# mach_dk_role.net
KiCad netlist of a schematic drawn in Altium Designer
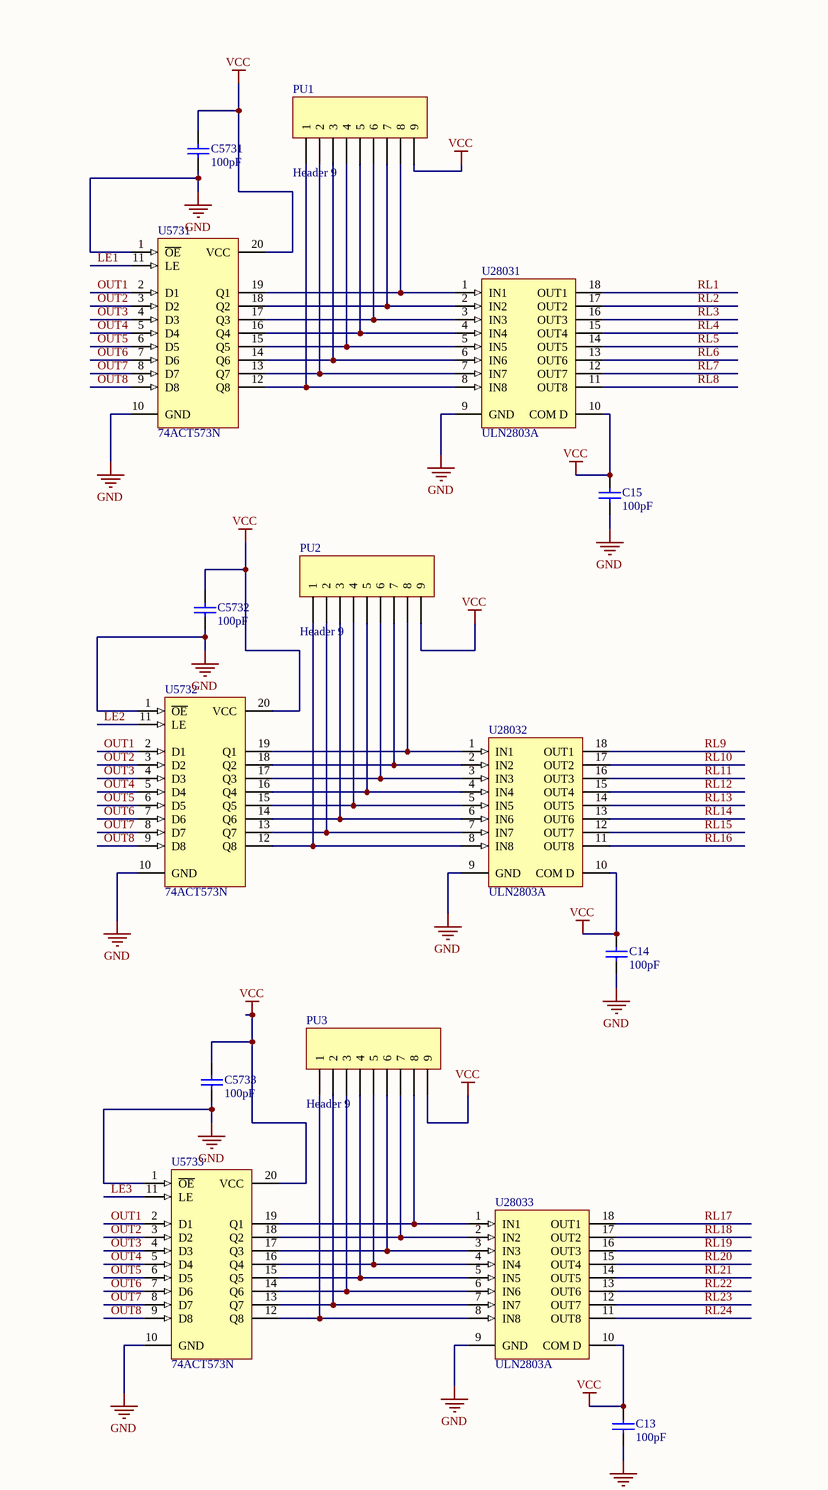
[diagram p0: mach dk role.SchDoc, top right]
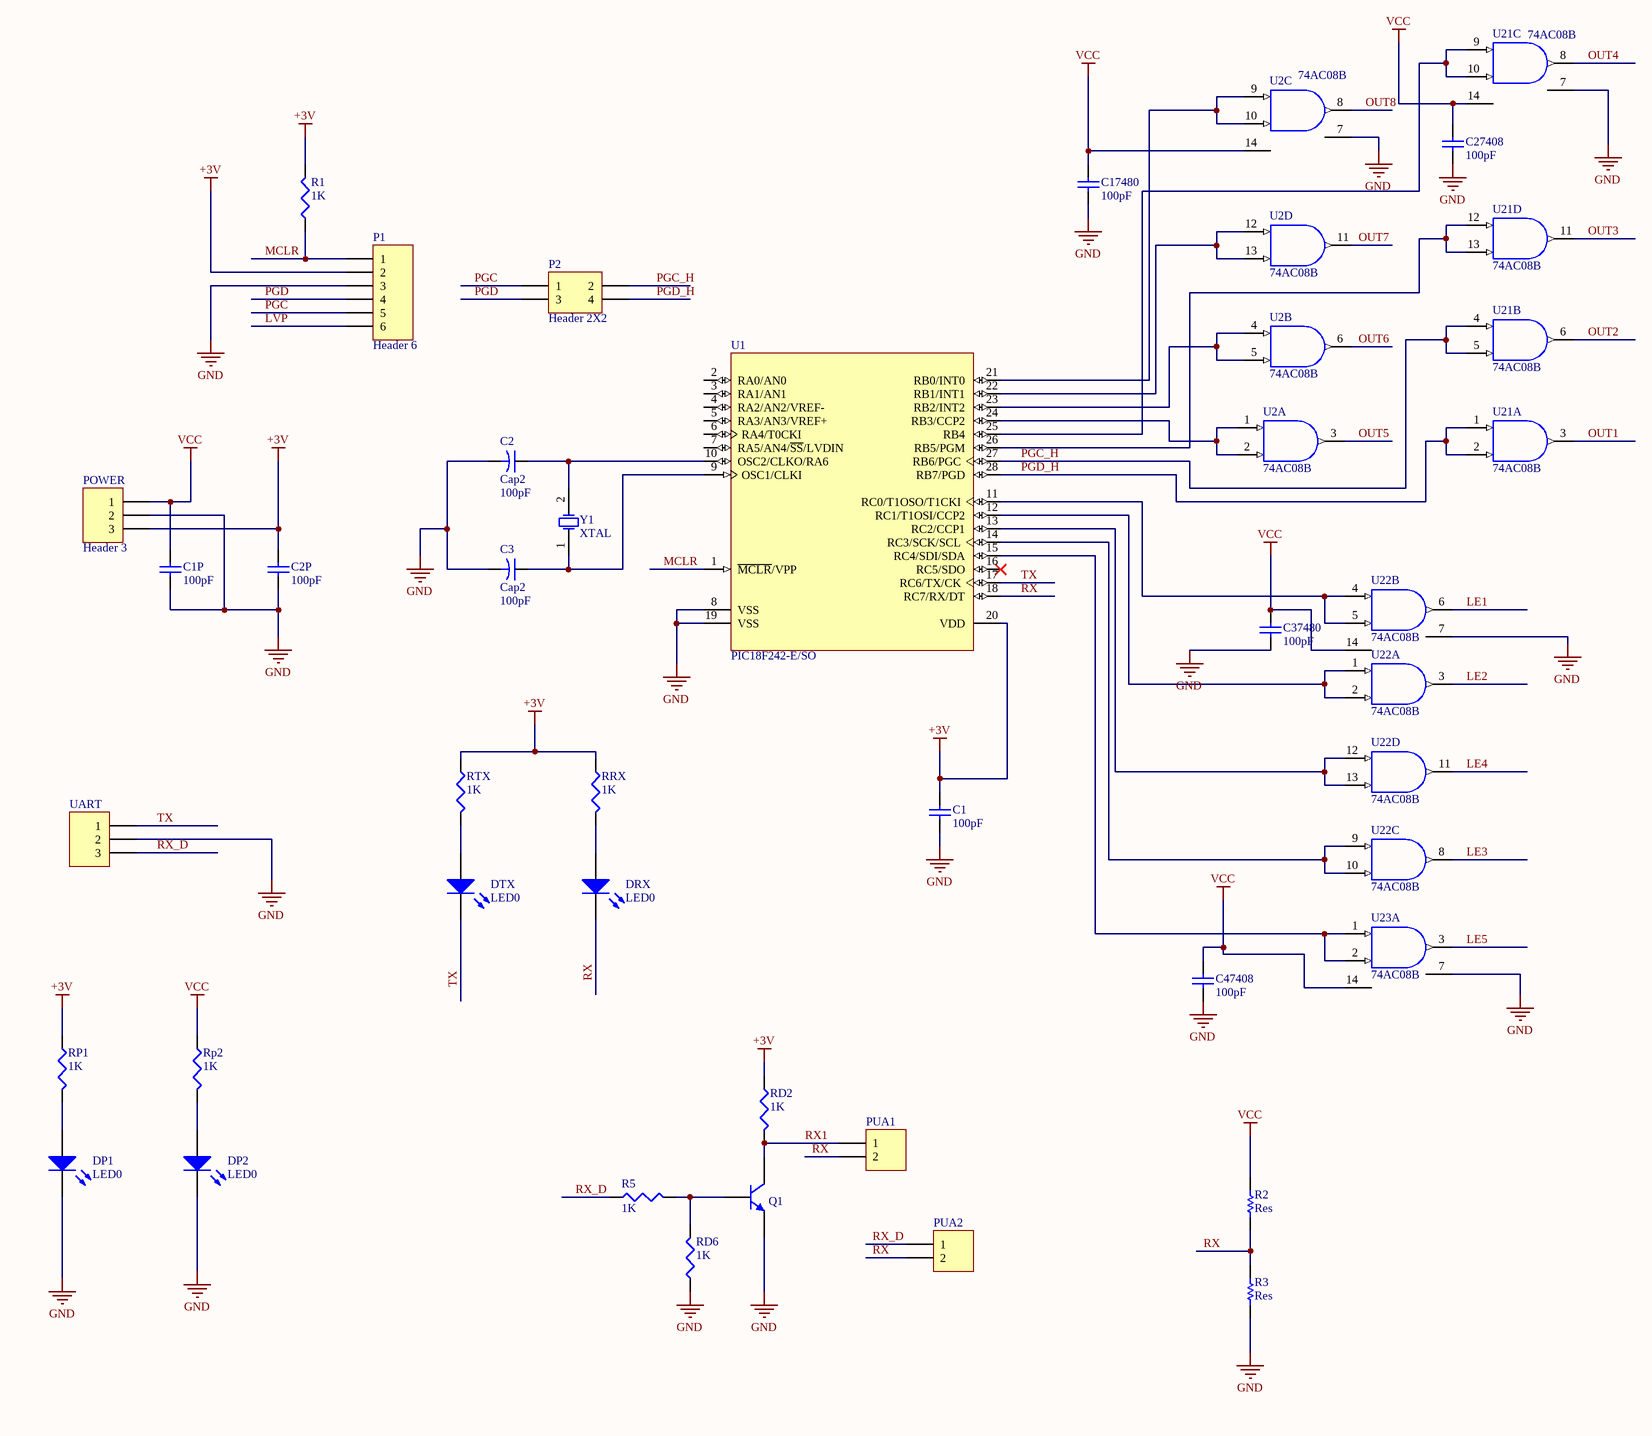
[diagram p1: mach dk role.SchDoc, bottom left]
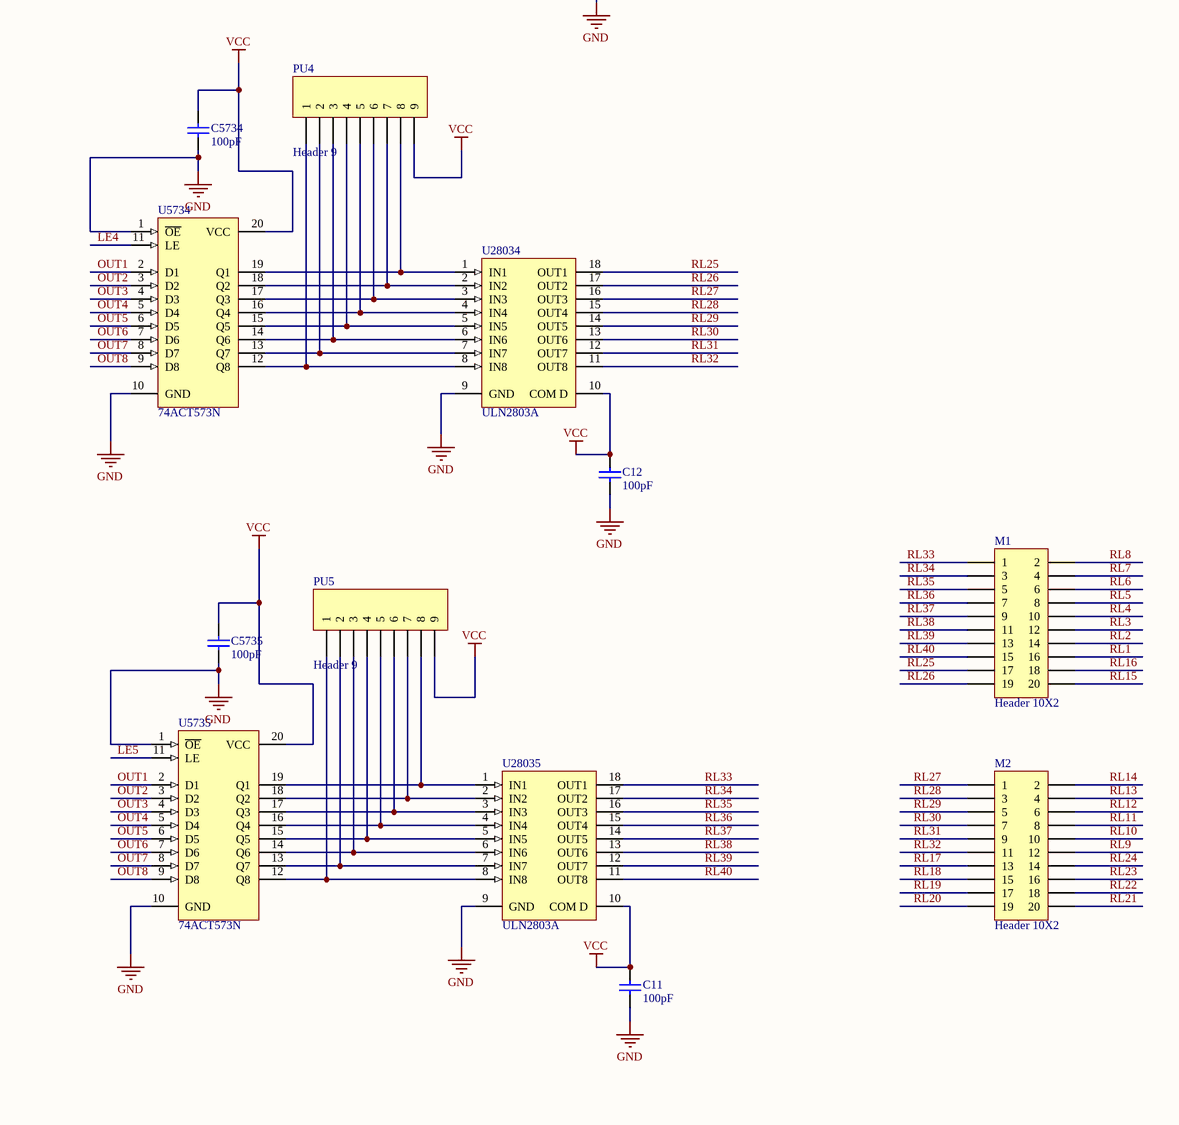
[diagram p2: mach dk role.SchDoc, bottom right]

(export (version "E")
  (design (tool "Eeschema 10.0.6"))
  (components
    (comp (ref "C1")
      (value "100pF")
      (footprint "RAD-0.3")
      (description "Capacitor")
      (fields (field (name "Comment") "Cap") (field (name "PUBLISHER") "Altium Limited"))
      (libsource (lib "Miscellaneous Devices") (part "Cap"))
    )
    (comp (ref "C1P")
      (value "100pF")
      (footprint "RAD-0.3")
      (description "Capacitor")
      (fields (field (name "Comment") "Cap") (field (name "PUBLISHER") "Altium Limited"))
      (libsource (lib "Miscellaneous Devices") (part "Cap"))
    )
    (comp (ref "C2")
      (value "Cap2")
      (footprint "CAPR5-4X5")
      (description "Capacitor")
      (fields (field (name "ALTIUM_VALUE") "100pF") (field (name "PUBLISHER") "Altium Limited"))
      (libsource (lib "Miscellaneous Devices") (part "Cap2"))
    )
    (comp (ref "C2P")
      (value "100pF")
      (footprint "RAD-0.3")
      (description "Capacitor")
      (fields (field (name "Comment") "Cap") (field (name "PUBLISHER") "Altium Limited"))
      (libsource (lib "Miscellaneous Devices") (part "Cap"))
    )
    (comp (ref "C3")
      (value "Cap2")
      (footprint "CAPR5-4X5")
      (description "Capacitor")
      (fields (field (name "ALTIUM_VALUE") "100pF") (field (name "PUBLISHER") "Altium Limited"))
      (libsource (lib "Miscellaneous Devices") (part "Cap2"))
    )
    (comp (ref "C11")
      (value "100pF")
      (footprint "RAD-0.3")
      (description "Capacitor")
      (fields (field (name "Comment") "Cap") (field (name "PUBLISHER") "Altium Limited"))
      (libsource (lib "Miscellaneous Devices") (part "Cap"))
    )
    (comp (ref "C12")
      (value "100pF")
      (footprint "RAD-0.3")
      (description "Capacitor")
      (fields (field (name "Comment") "Cap") (field (name "PUBLISHER") "Altium Limited"))
      (libsource (lib "Miscellaneous Devices") (part "Cap"))
    )
    (comp (ref "C13")
      (value "100pF")
      (footprint "RAD-0.3")
      (description "Capacitor")
      (fields (field (name "Comment") "Cap") (field (name "PUBLISHER") "Altium Limited"))
      (libsource (lib "Miscellaneous Devices") (part "Cap"))
    )
    (comp (ref "C14")
      (value "100pF")
      (footprint "RAD-0.3")
      (description "Capacitor")
      (fields (field (name "Comment") "Cap") (field (name "PUBLISHER") "Altium Limited"))
      (libsource (lib "Miscellaneous Devices") (part "Cap"))
    )
    (comp (ref "C15")
      (value "100pF")
      (footprint "RAD-0.3")
      (description "Capacitor")
      (fields (field (name "Comment") "Cap") (field (name "PUBLISHER") "Altium Limited"))
      (libsource (lib "Miscellaneous Devices") (part "Cap"))
    )
    (comp (ref "C5731")
      (value "100pF")
      (footprint "RAD-0.3")
      (description "Capacitor")
      (fields (field (name "Comment") "Cap") (field (name "PUBLISHER") "Altium Limited"))
      (libsource (lib "Miscellaneous Devices") (part "Cap"))
    )
    (comp (ref "C5732")
      (value "100pF")
      (footprint "RAD-0.3")
      (description "Capacitor")
      (fields (field (name "Comment") "Cap") (field (name "PUBLISHER") "Altium Limited"))
      (libsource (lib "Miscellaneous Devices") (part "Cap"))
    )
    (comp (ref "C5733")
      (value "100pF")
      (footprint "RAD-0.3")
      (description "Capacitor")
      (fields (field (name "Comment") "Cap") (field (name "PUBLISHER") "Altium Limited"))
      (libsource (lib "Miscellaneous Devices") (part "Cap"))
    )
    (comp (ref "C5734")
      (value "100pF")
      (footprint "RAD-0.3")
      (description "Capacitor")
      (fields (field (name "Comment") "Cap") (field (name "PUBLISHER") "Altium Limited"))
      (libsource (lib "Miscellaneous Devices") (part "Cap"))
    )
    (comp (ref "C5735")
      (value "100pF")
      (footprint "RAD-0.3")
      (description "Capacitor")
      (fields (field (name "Comment") "Cap") (field (name "PUBLISHER") "Altium Limited"))
      (libsource (lib "Miscellaneous Devices") (part "Cap"))
    )
    (comp (ref "C17480")
      (value "100pF")
      (footprint "RAD-0.3")
      (description "Capacitor")
      (fields (field (name "Comment") "Cap") (field (name "PUBLISHER") "Altium Limited"))
      (libsource (lib "Miscellaneous Devices") (part "Cap"))
    )
    (comp (ref "C27408")
      (value "100pF")
      (footprint "RAD-0.3")
      (description "Capacitor")
      (fields (field (name "Comment") "Cap") (field (name "PUBLISHER") "Altium Limited"))
      (libsource (lib "Miscellaneous Devices") (part "Cap"))
    )
    (comp (ref "C37480")
      (value "100pF")
      (footprint "RAD-0.3")
      (description "Capacitor")
      (fields (field (name "Comment") "Cap") (field (name "PUBLISHER") "Altium Limited"))
      (libsource (lib "Miscellaneous Devices") (part "Cap"))
    )
    (comp (ref "C47408")
      (value "100pF")
      (footprint "RAD-0.3")
      (description "Capacitor")
      (fields (field (name "Comment") "Cap") (field (name "PUBLISHER") "Altium Limited"))
      (libsource (lib "Miscellaneous Devices") (part "Cap"))
    )
    (comp (ref "DP1")
      (value "LED0")
      (footprint "LED-0")
      (description "Typical INFRARED GaAs LED")
      (fields (field (name "PUBLISHER") "Altium Limited"))
      (libsource (lib "Miscellaneous Devices") (part "LED0"))
    )
    (comp (ref "DP2")
      (value "LED0")
      (footprint "LED-0")
      (description "Typical INFRARED GaAs LED")
      (fields (field (name "PUBLISHER") "Altium Limited"))
      (libsource (lib "Miscellaneous Devices") (part "LED0"))
    )
    (comp (ref "DRX")
      (value "LED0")
      (footprint "LED-0")
      (description "Typical INFRARED GaAs LED")
      (fields (field (name "PUBLISHER") "Altium Limited"))
      (libsource (lib "Miscellaneous Devices") (part "LED0"))
    )
    (comp (ref "DTX")
      (value "LED0")
      (footprint "LED-0")
      (description "Typical INFRARED GaAs LED")
      (fields (field (name "PUBLISHER") "Altium Limited"))
      (libsource (lib "Miscellaneous Devices") (part "LED0"))
    )
    (comp (ref "M1")
      (value "Header 10X2")
      (footprint "HDR2X10")
      (description "Header, 10-Pin, Dual row")
      (fields (field (name "PUBLISHER") "Altium Limited"))
      (libsource (lib "Miscellaneous Connectors") (part "Header 10X2"))
    )
    (comp (ref "M2")
      (value "Header 10X2")
      (footprint "HDR2X10")
      (description "Header, 10-Pin, Dual row")
      (fields (field (name "PUBLISHER") "Altium Limited"))
      (libsource (lib "Miscellaneous Connectors") (part "Header 10X2"))
    )
    (comp (ref "P1")
      (value "Header 6")
      (footprint "HDR1X6")
      (description "Header, 6-Pin")
      (fields (field (name "PUBLISHER") "Altium Limited"))
      (libsource (lib "Miscellaneous Connectors") (part "Header 6"))
    )
    (comp (ref "P2")
      (value "Header 2X2")
      (footprint "HDR2X2")
      (description "Header, 2-Pin, Dual row")
      (fields (field (name "PUBLISHER") "Altium Limited"))
      (libsource (lib "Miscellaneous Connectors") (part "Header 2X2"))
    )
    (comp (ref "POWER")
      (value "Header 3")
      (footprint "HDR1X3")
      (description "Header, 3-Pin")
      (fields (field (name "PUBLISHER") "Altium Limited"))
      (libsource (lib "Miscellaneous Connectors") (part "Header 3"))
    )
    (comp (ref "PU1")
      (value "Header 9")
      (footprint "HDR1X9")
      (description "Header, 9-Pin")
      (fields (field (name "PUBLISHER") "Altium Limited"))
      (libsource (lib "Miscellaneous Connectors") (part "Header 9"))
    )
    (comp (ref "PU2")
      (value "Header 9")
      (footprint "HDR1X9")
      (description "Header, 9-Pin")
      (fields (field (name "PUBLISHER") "Altium Limited"))
      (libsource (lib "Miscellaneous Connectors") (part "Header 9"))
    )
    (comp (ref "PU3")
      (value "Header 9")
      (footprint "HDR1X9")
      (description "Header, 9-Pin")
      (fields (field (name "PUBLISHER") "Altium Limited"))
      (libsource (lib "Miscellaneous Connectors") (part "Header 9"))
    )
    (comp (ref "PU4")
      (value "Header 9")
      (footprint "HDR1X9")
      (description "Header, 9-Pin")
      (fields (field (name "PUBLISHER") "Altium Limited"))
      (libsource (lib "Miscellaneous Connectors") (part "Header 9"))
    )
    (comp (ref "PU5")
      (value "Header 9")
      (footprint "HDR1X9")
      (description "Header, 9-Pin")
      (fields (field (name "PUBLISHER") "Altium Limited"))
      (libsource (lib "Miscellaneous Connectors") (part "Header 9"))
    )
    (comp (ref "PUA1")
      (value "Header 2")
      (footprint "HDR1X2")
      (description "Header, 2-Pin")
      (fields (field (name "PUBLISHER") "Altium Limited"))
      (libsource (lib "Miscellaneous Connectors") (part "Header 2"))
    )
    (comp (ref "PUA2")
      (value "Header 2")
      (footprint "HDR1X2")
      (description "Header, 2-Pin")
      (fields (field (name "PUBLISHER") "Altium Limited"))
      (libsource (lib "Miscellaneous Connectors") (part "Header 2"))
    )
    (comp (ref "Q1")
      (value "C1815")
      (footprint "Device:C1815")
      (libsource (lib "Device_Component") (part "C1815"))
    )
    (comp (ref "R1")
      (value "1K")
      (footprint "J1-0603")
      (description "Resistor")
      (fields (field (name "Comment") "Res3") (field (name "PUBLISHER") "Altium Limited"))
      (libsource (lib "Miscellaneous Devices") (part "Res3"))
    )
    (comp (ref "R2")
      (value "Res")
      (footprint "Device:R_Nor")
      (libsource (lib "Device_Component") (part "Res"))
    )
    (comp (ref "R3")
      (value "Res")
      (footprint "Device:R_Nor")
      (libsource (lib "Device_Component") (part "Res"))
    )
    (comp (ref "R5")
      (value "1K")
      (footprint "J1-0603")
      (description "Resistor")
      (fields (field (name "Comment") "Res3") (field (name "PUBLISHER") "Altium Limited"))
      (libsource (lib "Miscellaneous Devices") (part "Res3"))
    )
    (comp (ref "RD2")
      (value "1K")
      (footprint "J1-0603")
      (description "Resistor")
      (fields (field (name "Comment") "Res3") (field (name "PUBLISHER") "Altium Limited"))
      (libsource (lib "Miscellaneous Devices") (part "Res3"))
    )
    (comp (ref "RD6")
      (value "1K")
      (footprint "J1-0603")
      (description "Resistor")
      (fields (field (name "Comment") "Res3") (field (name "PUBLISHER") "Altium Limited"))
      (libsource (lib "Miscellaneous Devices") (part "Res3"))
    )
    (comp (ref "RP1")
      (value "1K")
      (footprint "J1-0603")
      (description "Resistor")
      (fields (field (name "Comment") "Res3") (field (name "PUBLISHER") "Altium Limited"))
      (libsource (lib "Miscellaneous Devices") (part "Res3"))
    )
    (comp (ref "Rp2")
      (value "1K")
      (footprint "J1-0603")
      (description "Resistor")
      (fields (field (name "Comment") "Res3") (field (name "PUBLISHER") "Altium Limited"))
      (libsource (lib "Miscellaneous Devices") (part "Res3"))
    )
    (comp (ref "RRX")
      (value "1K")
      (footprint "J1-0603")
      (description "Resistor")
      (fields (field (name "Comment") "Res3") (field (name "PUBLISHER") "Altium Limited"))
      (libsource (lib "Miscellaneous Devices") (part "Res3"))
    )
    (comp (ref "RTX")
      (value "1K")
      (footprint "J1-0603")
      (description "Resistor")
      (fields (field (name "Comment") "Res3") (field (name "PUBLISHER") "Altium Limited"))
      (libsource (lib "Miscellaneous Devices") (part "Res3"))
    )
    (comp (ref "U1")
      (value "PIC18F242-E/SO")
      (footprint "SOIC300-28_N")
      (fields (field (name "PUBLISHER") "Altium Limited"))
      (libsource (lib "Microchip Microcontroller 8-Bit PIC18") (part "PIC18F242-E/SO"))
    )
    (comp (ref "U2")
      (value "74AC08B")
      (footprint "DIP14")
      (description "Quad 2-Input AND Gate")
      (fields (field (name "PUBLISHER") "Altium Limited"))
      (libsource (lib "ST Logic Gate") (part "74AC08B"))
    )
    (comp (ref "U21")
      (value "74AC08B")
      (footprint "DIP14")
      (description "Quad 2-Input AND Gate")
      (fields (field (name "PUBLISHER") "Altium Limited"))
      (libsource (lib "ST Logic Gate") (part "74AC08B"))
    )
    (comp (ref "U22")
      (value "74AC08B")
      (footprint "DIP14")
      (description "Quad 2-Input AND Gate")
      (fields (field (name "PUBLISHER") "Altium Limited"))
      (libsource (lib "ST Logic Gate") (part "74AC08B"))
    )
    (comp (ref "U23")
      (value "74AC08B")
      (footprint "DIP14")
      (description "Quad 2-Input AND Gate")
      (fields (field (name "PUBLISHER") "Altium Limited"))
      (libsource (lib "ST Logic Gate") (part "74AC08B"))
    )
    (comp (ref "U5731")
      (value "74ACT573N")
      (footprint "N020C")
      (description "Octal D-Type Transparent Latch with 3-State Outputs")
      (fields (field (name "PUBLISHER") "Altium Limited"))
      (libsource (lib "TI Logic Latch") (part "74ACT573N"))
    )
    (comp (ref "U5732")
      (value "74ACT573N")
      (footprint "N020C")
      (description "Octal D-Type Transparent Latch with 3-State Outputs")
      (fields (field (name "PUBLISHER") "Altium Limited"))
      (libsource (lib "TI Logic Latch") (part "74ACT573N"))
    )
    (comp (ref "U5733")
      (value "74ACT573N")
      (footprint "N020C")
      (description "Octal D-Type Transparent Latch with 3-State Outputs")
      (fields (field (name "PUBLISHER") "Altium Limited"))
      (libsource (lib "TI Logic Latch") (part "74ACT573N"))
    )
    (comp (ref "U5734")
      (value "74ACT573N")
      (footprint "N020C")
      (description "Octal D-Type Transparent Latch with 3-State Outputs")
      (fields (field (name "PUBLISHER") "Altium Limited"))
      (libsource (lib "TI Logic Latch") (part "74ACT573N"))
    )
    (comp (ref "U5735")
      (value "74ACT573N")
      (footprint "N020C")
      (description "Octal D-Type Transparent Latch with 3-State Outputs")
      (fields (field (name "PUBLISHER") "Altium Limited"))
      (libsource (lib "TI Logic Latch") (part "74ACT573N"))
    )
    (comp (ref "U28031")
      (value "ULN2803A")
      (footprint "DIP18")
      (description "Eight Darlington Array")
      (fields (field (name "PUBLISHER") "Altium Limited"))
      (libsource (lib "ST Interface Darlington Driver") (part "ULN2803A"))
    )
    (comp (ref "U28032")
      (value "ULN2803A")
      (footprint "DIP18")
      (description "Eight Darlington Array")
      (fields (field (name "PUBLISHER") "Altium Limited"))
      (libsource (lib "ST Interface Darlington Driver") (part "ULN2803A"))
    )
    (comp (ref "U28033")
      (value "ULN2803A")
      (footprint "DIP18")
      (description "Eight Darlington Array")
      (fields (field (name "PUBLISHER") "Altium Limited"))
      (libsource (lib "ST Interface Darlington Driver") (part "ULN2803A"))
    )
    (comp (ref "U28034")
      (value "ULN2803A")
      (footprint "DIP18")
      (description "Eight Darlington Array")
      (fields (field (name "PUBLISHER") "Altium Limited"))
      (libsource (lib "ST Interface Darlington Driver") (part "ULN2803A"))
    )
    (comp (ref "U28035")
      (value "ULN2803A")
      (footprint "DIP18")
      (description "Eight Darlington Array")
      (fields (field (name "PUBLISHER") "Altium Limited"))
      (libsource (lib "ST Interface Darlington Driver") (part "ULN2803A"))
    )
    (comp (ref "UART")
      (value "Header 3")
      (footprint "HDR1X3")
      (description "Header, 3-Pin")
      (fields (field (name "PUBLISHER") "Altium Limited"))
      (libsource (lib "Miscellaneous Connectors") (part "Header 3"))
    )
    (comp (ref "Y1")
      (value "XTAL")
      (footprint "R38")
      (description "Crystal Oscillator")
      (fields (field (name "PUBLISHER") "Altium Limited"))
      (libsource (lib "Miscellaneous Devices") (part "XTAL"))
    )
  )
  (nets
    (net (code "1") (name "+3V") (class "Default")
      (node (ref "C1") (pin "1") (pinfunction "1_1") (pintype "passive"))
      (node (ref "C2P") (pin "1") (pinfunction "1_1") (pintype "passive"))
      (node (ref "P1") (pin "2") (pinfunction "2_2") (pintype "passive"))
      (node (ref "POWER") (pin "3") (pinfunction "3_3") (pintype "passive"))
      (node (ref "R1") (pin "2") (pinfunction "2_2") (pintype "passive"))
      (node (ref "RD2") (pin "1") (pinfunction "1_1") (pintype "passive"))
      (node (ref "RP1") (pin "1") (pinfunction "1_1") (pintype "passive"))
      (node (ref "RRX") (pin "1") (pinfunction "1_1") (pintype "passive"))
      (node (ref "RTX") (pin "1") (pinfunction "1_1") (pintype "passive"))
      (node (ref "U1") (pin "20") (pinfunction "VDD_20") (pintype "power_in"))
    )
    (net (code "2") (name "/LE1") (class "Default")
      (node (ref "U22") (pin "6") (pinfunction "Y_6") (pintype "output"))
      (node (ref "U5731") (pin "11") (pinfunction "LE_11") (pintype "input"))
    )
    (net (code "3") (name "/LE2") (class "Default")
      (node (ref "U22") (pin "3") (pinfunction "Y_3") (pintype "output"))
      (node (ref "U5732") (pin "11") (pinfunction "LE_11") (pintype "input"))
    )
    (net (code "4") (name "/LE3") (class "Default")
      (node (ref "U22") (pin "8") (pinfunction "Y_8") (pintype "output"))
      (node (ref "U5733") (pin "11") (pinfunction "LE_11") (pintype "input"))
    )
    (net (code "5") (name "/LE4") (class "Default")
      (node (ref "U22") (pin "11") (pinfunction "Y_11") (pintype "output"))
      (node (ref "U5734") (pin "11") (pinfunction "LE_11") (pintype "input"))
    )
    (net (code "6") (name "/LE5") (class "Default")
      (node (ref "U23") (pin "3") (pinfunction "Y_3") (pintype "output"))
      (node (ref "U5735") (pin "11") (pinfunction "LE_11") (pintype "input"))
    )
    (net (code "7") (name "/LVP") (class "Default")
      (node (ref "P1") (pin "6") (pinfunction "6_6") (pintype "passive"))
    )
    (net (code "8") (name "/MCLR") (class "Default")
      (node (ref "P1") (pin "1") (pinfunction "1_1") (pintype "passive"))
      (node (ref "R1") (pin "1") (pinfunction "1_1") (pintype "passive"))
      (node (ref "U1") (pin "1") (pinfunction "~{MCLR}/VPP_1") (pintype "input"))
    )
    (net (code "9") (name "/OUT1") (class "Default")
      (node (ref "U21") (pin "3") (pinfunction "Y_3") (pintype "output"))
      (node (ref "U5731") (pin "2") (pinfunction "D1_2") (pintype "input"))
      (node (ref "U5732") (pin "2") (pinfunction "D1_2") (pintype "input"))
      (node (ref "U5733") (pin "2") (pinfunction "D1_2") (pintype "input"))
      (node (ref "U5734") (pin "2") (pinfunction "D1_2") (pintype "input"))
      (node (ref "U5735") (pin "2") (pinfunction "D1_2") (pintype "input"))
    )
    (net (code "10") (name "/OUT2") (class "Default")
      (node (ref "U21") (pin "6") (pinfunction "Y_6") (pintype "output"))
      (node (ref "U5731") (pin "3") (pinfunction "D2_3") (pintype "input"))
      (node (ref "U5732") (pin "3") (pinfunction "D2_3") (pintype "input"))
      (node (ref "U5733") (pin "3") (pinfunction "D2_3") (pintype "input"))
      (node (ref "U5734") (pin "3") (pinfunction "D2_3") (pintype "input"))
      (node (ref "U5735") (pin "3") (pinfunction "D2_3") (pintype "input"))
    )
    (net (code "11") (name "/OUT3") (class "Default")
      (node (ref "U21") (pin "11") (pinfunction "Y_11") (pintype "output"))
      (node (ref "U5731") (pin "4") (pinfunction "D3_4") (pintype "input"))
      (node (ref "U5732") (pin "4") (pinfunction "D3_4") (pintype "input"))
      (node (ref "U5733") (pin "4") (pinfunction "D3_4") (pintype "input"))
      (node (ref "U5734") (pin "4") (pinfunction "D3_4") (pintype "input"))
      (node (ref "U5735") (pin "4") (pinfunction "D3_4") (pintype "input"))
    )
    (net (code "12") (name "/OUT4") (class "Default")
      (node (ref "U21") (pin "8") (pinfunction "Y_8") (pintype "output"))
      (node (ref "U5731") (pin "5") (pinfunction "D4_5") (pintype "input"))
      (node (ref "U5732") (pin "5") (pinfunction "D4_5") (pintype "input"))
      (node (ref "U5733") (pin "5") (pinfunction "D4_5") (pintype "input"))
      (node (ref "U5734") (pin "5") (pinfunction "D4_5") (pintype "input"))
      (node (ref "U5735") (pin "5") (pinfunction "D4_5") (pintype "input"))
    )
    (net (code "13") (name "/OUT5") (class "Default")
      (node (ref "U2") (pin "3") (pinfunction "Y_3") (pintype "output"))
      (node (ref "U5731") (pin "6") (pinfunction "D5_6") (pintype "input"))
      (node (ref "U5732") (pin "6") (pinfunction "D5_6") (pintype "input"))
      (node (ref "U5733") (pin "6") (pinfunction "D5_6") (pintype "input"))
      (node (ref "U5734") (pin "6") (pinfunction "D5_6") (pintype "input"))
      (node (ref "U5735") (pin "6") (pinfunction "D5_6") (pintype "input"))
    )
    (net (code "14") (name "/OUT6") (class "Default")
      (node (ref "U2") (pin "6") (pinfunction "Y_6") (pintype "output"))
      (node (ref "U5731") (pin "7") (pinfunction "D6_7") (pintype "input"))
      (node (ref "U5732") (pin "7") (pinfunction "D6_7") (pintype "input"))
      (node (ref "U5733") (pin "7") (pinfunction "D6_7") (pintype "input"))
      (node (ref "U5734") (pin "7") (pinfunction "D6_7") (pintype "input"))
      (node (ref "U5735") (pin "7") (pinfunction "D6_7") (pintype "input"))
    )
    (net (code "15") (name "/OUT7") (class "Default")
      (node (ref "U2") (pin "11") (pinfunction "Y_11") (pintype "output"))
      (node (ref "U5731") (pin "8") (pinfunction "D7_8") (pintype "input"))
      (node (ref "U5732") (pin "8") (pinfunction "D7_8") (pintype "input"))
      (node (ref "U5733") (pin "8") (pinfunction "D7_8") (pintype "input"))
      (node (ref "U5734") (pin "8") (pinfunction "D7_8") (pintype "input"))
      (node (ref "U5735") (pin "8") (pinfunction "D7_8") (pintype "input"))
    )
    (net (code "16") (name "/OUT8") (class "Default")
      (node (ref "U2") (pin "8") (pinfunction "Y_8") (pintype "output"))
      (node (ref "U5731") (pin "9") (pinfunction "D8_9") (pintype "input"))
      (node (ref "U5732") (pin "9") (pinfunction "D8_9") (pintype "input"))
      (node (ref "U5733") (pin "9") (pinfunction "D8_9") (pintype "input"))
      (node (ref "U5734") (pin "9") (pinfunction "D8_9") (pintype "input"))
      (node (ref "U5735") (pin "9") (pinfunction "D8_9") (pintype "input"))
    )
    (net (code "17") (name "/PGC") (class "Default")
      (node (ref "P1") (pin "5") (pinfunction "5_5") (pintype "passive"))
      (node (ref "P2") (pin "1") (pinfunction "1_1") (pintype "passive"))
    )
    (net (code "18") (name "/PGC_H") (class "Default")
      (node (ref "P2") (pin "2") (pinfunction "2_2") (pintype "passive"))
      (node (ref "U1") (pin "27") (pinfunction "RB6/PGC_27") (pintype "bidirectional"))
      (node (ref "U21") (pin "4") (pinfunction "A_4") (pintype "input"))
      (node (ref "U21") (pin "5") (pinfunction "B_5") (pintype "input"))
    )
    (net (code "19") (name "/PGD") (class "Default")
      (node (ref "P1") (pin "4") (pinfunction "4_4") (pintype "passive"))
      (node (ref "P2") (pin "3") (pinfunction "3_3") (pintype "passive"))
    )
    (net (code "20") (name "/PGD_H") (class "Default")
      (node (ref "P2") (pin "4") (pinfunction "4_4") (pintype "passive"))
      (node (ref "U1") (pin "28") (pinfunction "RB7/PGD_28") (pintype "bidirectional"))
      (node (ref "U21") (pin "1") (pinfunction "A_1") (pintype "input"))
      (node (ref "U21") (pin "2") (pinfunction "B_2") (pintype "input"))
    )
    (net (code "21") (name "/RL1") (class "Default")
      (node (ref "M1") (pin "16") (pinfunction "16_16") (pintype "passive"))
      (node (ref "U28031") (pin "18") (pinfunction "OUT1_18") (pintype "open_collector"))
    )
    (net (code "22") (name "/RL2") (class "Default")
      (node (ref "M1") (pin "14") (pinfunction "14_14") (pintype "passive"))
      (node (ref "U28031") (pin "17") (pinfunction "OUT2_17") (pintype "open_collector"))
    )
    (net (code "23") (name "/RL3") (class "Default")
      (node (ref "M1") (pin "12") (pinfunction "12_12") (pintype "passive"))
      (node (ref "U28031") (pin "16") (pinfunction "OUT3_16") (pintype "open_collector"))
    )
    (net (code "24") (name "/RL4") (class "Default")
      (node (ref "M1") (pin "10") (pinfunction "10_10") (pintype "passive"))
      (node (ref "U28031") (pin "15") (pinfunction "OUT4_15") (pintype "open_collector"))
    )
    (net (code "25") (name "/RL5") (class "Default")
      (node (ref "M1") (pin "8") (pinfunction "8_8") (pintype "passive"))
      (node (ref "U28031") (pin "14") (pinfunction "OUT5_14") (pintype "open_collector"))
    )
    (net (code "26") (name "/RL6") (class "Default")
      (node (ref "M1") (pin "6") (pinfunction "6_6") (pintype "passive"))
      (node (ref "U28031") (pin "13") (pinfunction "OUT6_13") (pintype "open_collector"))
    )
    (net (code "27") (name "/RL7") (class "Default")
      (node (ref "M1") (pin "4") (pinfunction "4_4") (pintype "passive"))
      (node (ref "U28031") (pin "12") (pinfunction "OUT7_12") (pintype "open_collector"))
    )
    (net (code "28") (name "/RL8") (class "Default")
      (node (ref "M1") (pin "2") (pinfunction "2_2") (pintype "passive"))
      (node (ref "U28031") (pin "11") (pinfunction "OUT8_11") (pintype "open_collector"))
    )
    (net (code "29") (name "/RL9") (class "Default")
      (node (ref "M2") (pin "12") (pinfunction "12_12") (pintype "passive"))
      (node (ref "U28032") (pin "18") (pinfunction "OUT1_18") (pintype "open_collector"))
    )
    (net (code "30") (name "/RL10") (class "Default")
      (node (ref "M2") (pin "10") (pinfunction "10_10") (pintype "passive"))
      (node (ref "U28032") (pin "17") (pinfunction "OUT2_17") (pintype "open_collector"))
    )
    (net (code "31") (name "/RL11") (class "Default")
      (node (ref "M2") (pin "8") (pinfunction "8_8") (pintype "passive"))
      (node (ref "U28032") (pin "16") (pinfunction "OUT3_16") (pintype "open_collector"))
    )
    (net (code "32") (name "/RL12") (class "Default")
      (node (ref "M2") (pin "6") (pinfunction "6_6") (pintype "passive"))
      (node (ref "U28032") (pin "15") (pinfunction "OUT4_15") (pintype "open_collector"))
    )
    (net (code "33") (name "/RL13") (class "Default")
      (node (ref "M2") (pin "4") (pinfunction "4_4") (pintype "passive"))
      (node (ref "U28032") (pin "14") (pinfunction "OUT5_14") (pintype "open_collector"))
    )
    (net (code "34") (name "/RL14") (class "Default")
      (node (ref "M2") (pin "2") (pinfunction "2_2") (pintype "passive"))
      (node (ref "U28032") (pin "13") (pinfunction "OUT6_13") (pintype "open_collector"))
    )
    (net (code "35") (name "/RL15") (class "Default")
      (node (ref "M1") (pin "20") (pinfunction "20_20") (pintype "passive"))
      (node (ref "U28032") (pin "12") (pinfunction "OUT7_12") (pintype "open_collector"))
    )
    (net (code "36") (name "/RL16") (class "Default")
      (node (ref "M1") (pin "18") (pinfunction "18_18") (pintype "passive"))
      (node (ref "U28032") (pin "11") (pinfunction "OUT8_11") (pintype "open_collector"))
    )
    (net (code "37") (name "/RL17") (class "Default")
      (node (ref "M2") (pin "13") (pinfunction "13_13") (pintype "passive"))
      (node (ref "U28033") (pin "18") (pinfunction "OUT1_18") (pintype "open_collector"))
    )
    (net (code "38") (name "/RL18") (class "Default")
      (node (ref "M2") (pin "15") (pinfunction "15_15") (pintype "passive"))
      (node (ref "U28033") (pin "17") (pinfunction "OUT2_17") (pintype "open_collector"))
    )
    (net (code "39") (name "/RL19") (class "Default")
      (node (ref "M2") (pin "17") (pinfunction "17_17") (pintype "passive"))
      (node (ref "U28033") (pin "16") (pinfunction "OUT3_16") (pintype "open_collector"))
    )
    (net (code "40") (name "/RL20") (class "Default")
      (node (ref "M2") (pin "19") (pinfunction "19_19") (pintype "passive"))
      (node (ref "U28033") (pin "15") (pinfunction "OUT4_15") (pintype "open_collector"))
    )
    (net (code "41") (name "/RL21") (class "Default")
      (node (ref "M2") (pin "20") (pinfunction "20_20") (pintype "passive"))
      (node (ref "U28033") (pin "14") (pinfunction "OUT5_14") (pintype "open_collector"))
    )
    (net (code "42") (name "/RL22") (class "Default")
      (node (ref "M2") (pin "18") (pinfunction "18_18") (pintype "passive"))
      (node (ref "U28033") (pin "13") (pinfunction "OUT6_13") (pintype "open_collector"))
    )
    (net (code "43") (name "/RL23") (class "Default")
      (node (ref "M2") (pin "16") (pinfunction "16_16") (pintype "passive"))
      (node (ref "U28033") (pin "12") (pinfunction "OUT7_12") (pintype "open_collector"))
    )
    (net (code "44") (name "/RL24") (class "Default")
      (node (ref "M2") (pin "14") (pinfunction "14_14") (pintype "passive"))
      (node (ref "U28033") (pin "11") (pinfunction "OUT8_11") (pintype "open_collector"))
    )
    (net (code "45") (name "/RL25") (class "Default")
      (node (ref "M1") (pin "17") (pinfunction "17_17") (pintype "passive"))
      (node (ref "U28034") (pin "18") (pinfunction "OUT1_18") (pintype "open_collector"))
    )
    (net (code "46") (name "/RL26") (class "Default")
      (node (ref "M1") (pin "19") (pinfunction "19_19") (pintype "passive"))
      (node (ref "U28034") (pin "17") (pinfunction "OUT2_17") (pintype "open_collector"))
    )
    (net (code "47") (name "/RL27") (class "Default")
      (node (ref "M2") (pin "1") (pinfunction "1_1") (pintype "passive"))
      (node (ref "U28034") (pin "16") (pinfunction "OUT3_16") (pintype "open_collector"))
    )
    (net (code "48") (name "/RL28") (class "Default")
      (node (ref "M2") (pin "3") (pinfunction "3_3") (pintype "passive"))
      (node (ref "U28034") (pin "15") (pinfunction "OUT4_15") (pintype "open_collector"))
    )
    (net (code "49") (name "/RL29") (class "Default")
      (node (ref "M2") (pin "5") (pinfunction "5_5") (pintype "passive"))
      (node (ref "U28034") (pin "14") (pinfunction "OUT5_14") (pintype "open_collector"))
    )
    (net (code "50") (name "/RL30") (class "Default")
      (node (ref "M2") (pin "7") (pinfunction "7_7") (pintype "passive"))
      (node (ref "U28034") (pin "13") (pinfunction "OUT6_13") (pintype "open_collector"))
    )
    (net (code "51") (name "/RL31") (class "Default")
      (node (ref "M2") (pin "9") (pinfunction "9_9") (pintype "passive"))
      (node (ref "U28034") (pin "12") (pinfunction "OUT7_12") (pintype "open_collector"))
    )
    (net (code "52") (name "/RL32") (class "Default")
      (node (ref "M2") (pin "11") (pinfunction "11_11") (pintype "passive"))
      (node (ref "U28034") (pin "11") (pinfunction "OUT8_11") (pintype "open_collector"))
    )
    (net (code "53") (name "/RL33") (class "Default")
      (node (ref "M1") (pin "1") (pinfunction "1_1") (pintype "passive"))
      (node (ref "U28035") (pin "18") (pinfunction "OUT1_18") (pintype "open_collector"))
    )
    (net (code "54") (name "/RL34") (class "Default")
      (node (ref "M1") (pin "3") (pinfunction "3_3") (pintype "passive"))
      (node (ref "U28035") (pin "17") (pinfunction "OUT2_17") (pintype "open_collector"))
    )
    (net (code "55") (name "/RL35") (class "Default")
      (node (ref "M1") (pin "5") (pinfunction "5_5") (pintype "passive"))
      (node (ref "U28035") (pin "16") (pinfunction "OUT3_16") (pintype "open_collector"))
    )
    (net (code "56") (name "/RL36") (class "Default")
      (node (ref "M1") (pin "7") (pinfunction "7_7") (pintype "passive"))
      (node (ref "U28035") (pin "15") (pinfunction "OUT4_15") (pintype "open_collector"))
    )
    (net (code "57") (name "/RL37") (class "Default")
      (node (ref "M1") (pin "9") (pinfunction "9_9") (pintype "passive"))
      (node (ref "U28035") (pin "14") (pinfunction "OUT5_14") (pintype "open_collector"))
    )
    (net (code "58") (name "/RL38") (class "Default")
      (node (ref "M1") (pin "11") (pinfunction "11_11") (pintype "passive"))
      (node (ref "U28035") (pin "13") (pinfunction "OUT6_13") (pintype "open_collector"))
    )
    (net (code "59") (name "/RL39") (class "Default")
      (node (ref "M1") (pin "13") (pinfunction "13_13") (pintype "passive"))
      (node (ref "U28035") (pin "12") (pinfunction "OUT7_12") (pintype "open_collector"))
    )
    (net (code "60") (name "/RL40") (class "Default")
      (node (ref "M1") (pin "15") (pinfunction "15_15") (pintype "passive"))
      (node (ref "U28035") (pin "11") (pinfunction "OUT8_11") (pintype "open_collector"))
    )
    (net (code "61") (name "/RX") (class "Default")
      (node (ref "DRX") (pin "2") (pinfunction "K_2") (pintype "passive"))
      (node (ref "PUA1") (pin "2") (pinfunction "2_2") (pintype "passive"))
      (node (ref "PUA2") (pin "2") (pinfunction "2_2") (pintype "passive"))
      (node (ref "R2") (pin "1") (pinfunction "1_1") (pintype "passive"))
      (node (ref "R3") (pin "2") (pinfunction "2_2") (pintype "passive"))
      (node (ref "U1") (pin "18") (pinfunction "RC7/RX/DT_18") (pintype "bidirectional"))
    )
    (net (code "62") (name "/RX1") (class "Default")
      (node (ref "PUA1") (pin "1") (pinfunction "1_1") (pintype "passive"))
      (node (ref "Q1") (pin "2") (pinfunction "C_2") (pintype "passive"))
      (node (ref "RD2") (pin "2") (pinfunction "2_2") (pintype "passive"))
    )
    (net (code "63") (name "/RX_D") (class "Default")
      (node (ref "PUA2") (pin "1") (pinfunction "1_1") (pintype "passive"))
      (node (ref "R5") (pin "1") (pinfunction "1_1") (pintype "passive"))
      (node (ref "UART") (pin "3") (pinfunction "3_3") (pintype "passive"))
    )
    (net (code "64") (name "/TX") (class "Default")
      (node (ref "DTX") (pin "2") (pinfunction "K_2") (pintype "passive"))
      (node (ref "U1") (pin "17") (pinfunction "RC6/TX/CK_17") (pintype "bidirectional"))
      (node (ref "UART") (pin "1") (pinfunction "1_1") (pintype "passive"))
    )
    (net (code "65") (name "GND") (class "Default")
      (node (ref "C1") (pin "2") (pinfunction "2_2") (pintype "passive"))
      (node (ref "C11") (pin "2") (pinfunction "2_2") (pintype "passive"))
      (node (ref "C12") (pin "2") (pinfunction "2_2") (pintype "passive"))
      (node (ref "C13") (pin "2") (pinfunction "2_2") (pintype "passive"))
      (node (ref "C14") (pin "2") (pinfunction "2_2") (pintype "passive"))
      (node (ref "C15") (pin "2") (pinfunction "2_2") (pintype "passive"))
      (node (ref "C17480") (pin "2") (pinfunction "2_2") (pintype "passive"))
      (node (ref "C1P") (pin "2") (pinfunction "2_2") (pintype "passive"))
      (node (ref "C2") (pin "2") (pinfunction "2_2") (pintype "passive"))
      (node (ref "C27408") (pin "2") (pinfunction "2_2") (pintype "passive"))
      (node (ref "C2P") (pin "2") (pinfunction "2_2") (pintype "passive"))
      (node (ref "C3") (pin "2") (pinfunction "2_2") (pintype "passive"))
      (node (ref "C37480") (pin "2") (pinfunction "2_2") (pintype "passive"))
      (node (ref "C47408") (pin "2") (pinfunction "2_2") (pintype "passive"))
      (node (ref "C5731") (pin "2") (pinfunction "2_2") (pintype "passive"))
      (node (ref "C5732") (pin "2") (pinfunction "2_2") (pintype "passive"))
      (node (ref "C5733") (pin "2") (pinfunction "2_2") (pintype "passive"))
      (node (ref "C5734") (pin "2") (pinfunction "2_2") (pintype "passive"))
      (node (ref "C5735") (pin "2") (pinfunction "2_2") (pintype "passive"))
      (node (ref "DP1") (pin "2") (pinfunction "K_2") (pintype "passive"))
      (node (ref "DP2") (pin "2") (pinfunction "K_2") (pintype "passive"))
      (node (ref "P1") (pin "3") (pinfunction "3_3") (pintype "passive"))
      (node (ref "POWER") (pin "2") (pinfunction "2_2") (pintype "passive"))
      (node (ref "Q1") (pin "1") (pinfunction "E_1") (pintype "passive"))
      (node (ref "R3") (pin "1") (pinfunction "1_1") (pintype "passive"))
      (node (ref "RD6") (pin "1") (pinfunction "1_1") (pintype "passive"))
      (node (ref "U1") (pin "19") (pinfunction "VSS_19") (pintype "power_in"))
      (node (ref "U1") (pin "8") (pinfunction "VSS_8") (pintype "power_in"))
      (node (ref "U2") (pin "7") (pinfunction "GND_7") (pintype "power_in"))
      (node (ref "U21") (pin "7") (pinfunction "GND_7") (pintype "power_in"))
      (node (ref "U22") (pin "7") (pinfunction "GND_7") (pintype "power_in"))
      (node (ref "U23") (pin "7") (pinfunction "GND_7") (pintype "power_in"))
      (node (ref "U28031") (pin "9") (pinfunction "GND_9") (pintype "power_in"))
      (node (ref "U28032") (pin "9") (pinfunction "GND_9") (pintype "power_in"))
      (node (ref "U28033") (pin "9") (pinfunction "GND_9") (pintype "power_in"))
      (node (ref "U28034") (pin "9") (pinfunction "GND_9") (pintype "power_in"))
      (node (ref "U28035") (pin "9") (pinfunction "GND_9") (pintype "power_in"))
      (node (ref "U5731") (pin "1") (pinfunction "~{OE}_1") (pintype "input"))
      (node (ref "U5731") (pin "10") (pinfunction "GND_10") (pintype "power_in"))
      (node (ref "U5732") (pin "1") (pinfunction "~{OE}_1") (pintype "input"))
      (node (ref "U5732") (pin "10") (pinfunction "GND_10") (pintype "power_in"))
      (node (ref "U5733") (pin "1") (pinfunction "~{OE}_1") (pintype "input"))
      (node (ref "U5733") (pin "10") (pinfunction "GND_10") (pintype "power_in"))
      (node (ref "U5734") (pin "1") (pinfunction "~{OE}_1") (pintype "input"))
      (node (ref "U5734") (pin "10") (pinfunction "GND_10") (pintype "power_in"))
      (node (ref "U5735") (pin "1") (pinfunction "~{OE}_1") (pintype "input"))
      (node (ref "U5735") (pin "10") (pinfunction "GND_10") (pintype "power_in"))
      (node (ref "UART") (pin "2") (pinfunction "2_2") (pintype "passive"))
    )
    (net (code "66") (name "Net-(DP1-A)") (class "Default")
      (node (ref "DP1") (pin "1") (pinfunction "A_1") (pintype "passive"))
      (node (ref "RP1") (pin "2") (pinfunction "2_2") (pintype "passive"))
    )
    (net (code "67") (name "Net-(DP2-A)") (class "Default")
      (node (ref "DP2") (pin "1") (pinfunction "A_1") (pintype "passive"))
      (node (ref "Rp2") (pin "2") (pinfunction "2_2") (pintype "passive"))
    )
    (net (code "68") (name "Net-(DRX-A)") (class "Default")
      (node (ref "DRX") (pin "1") (pinfunction "A_1") (pintype "passive"))
      (node (ref "RRX") (pin "2") (pinfunction "2_2") (pintype "passive"))
    )
    (net (code "69") (name "Net-(DTX-A)") (class "Default")
      (node (ref "DTX") (pin "1") (pinfunction "A_1") (pintype "passive"))
      (node (ref "RTX") (pin "2") (pinfunction "2_2") (pintype "passive"))
    )
    (net (code "70") (name "Net-(Q1-B)") (class "Default")
      (node (ref "Q1") (pin "3") (pinfunction "B_3") (pintype "passive"))
      (node (ref "R5") (pin "2") (pinfunction "2_2") (pintype "passive"))
      (node (ref "RD6") (pin "2") (pinfunction "2_2") (pintype "passive"))
    )
    (net (code "71") (name "Net-(U1-OSC1{slash}CLKI)") (class "Default")
      (node (ref "C3") (pin "1") (pinfunction "1_1") (pintype "passive"))
      (node (ref "U1") (pin "9") (pinfunction "OSC1/CLKI_9") (pintype "input"))
      (node (ref "Y1") (pin "1") (pinfunction "OSC1_1") (pintype "passive"))
    )
    (net (code "72") (name "Net-(U1-OSC2{slash}CLKO{slash}RA6)") (class "Default")
      (node (ref "C2") (pin "1") (pinfunction "1_1") (pintype "passive"))
      (node (ref "U1") (pin "10") (pinfunction "OSC2/CLKO/RA6_10") (pintype "bidirectional"))
      (node (ref "Y1") (pin "2") (pinfunction "OSC2_2") (pintype "passive"))
    )
    (net (code "73") (name "Net-(U1-RB0{slash}INT0)") (class "Default")
      (node (ref "U1") (pin "21") (pinfunction "RB0/INT0_21") (pintype "bidirectional"))
      (node (ref "U2") (pin "10") (pinfunction "B_10") (pintype "input"))
      (node (ref "U2") (pin "9") (pinfunction "A_9") (pintype "input"))
    )
    (net (code "74") (name "Net-(U1-RB1{slash}INT1)") (class "Default")
      (node (ref "U1") (pin "22") (pinfunction "RB1/INT1_22") (pintype "bidirectional"))
      (node (ref "U2") (pin "12") (pinfunction "A_12") (pintype "input"))
      (node (ref "U2") (pin "13") (pinfunction "B_13") (pintype "input"))
    )
    (net (code "75") (name "Net-(U1-RB2{slash}INT2)") (class "Default")
      (node (ref "U1") (pin "23") (pinfunction "RB2/INT2_23") (pintype "bidirectional"))
      (node (ref "U2") (pin "4") (pinfunction "A_4") (pintype "input"))
      (node (ref "U2") (pin "5") (pinfunction "B_5") (pintype "input"))
    )
    (net (code "76") (name "Net-(U1-RB3{slash}CCP2)") (class "Default")
      (node (ref "U1") (pin "24") (pinfunction "RB3/CCP2_24") (pintype "bidirectional"))
      (node (ref "U2") (pin "1") (pinfunction "A_1") (pintype "input"))
      (node (ref "U2") (pin "2") (pinfunction "B_2") (pintype "input"))
    )
    (net (code "77") (name "Net-(U1-RB4)") (class "Default")
      (node (ref "U1") (pin "25") (pinfunction "RB4_25") (pintype "bidirectional"))
      (node (ref "U21") (pin "10") (pinfunction "B_10") (pintype "input"))
      (node (ref "U21") (pin "9") (pinfunction "A_9") (pintype "input"))
    )
    (net (code "78") (name "Net-(U1-RB5{slash}PGM)") (class "Default")
      (node (ref "U1") (pin "26") (pinfunction "RB5/PGM_26") (pintype "bidirectional"))
      (node (ref "U21") (pin "12") (pinfunction "A_12") (pintype "input"))
      (node (ref "U21") (pin "13") (pinfunction "B_13") (pintype "input"))
    )
    (net (code "79") (name "Net-(U1-RC0{slash}T1OSO{slash}T1CKI)") (class "Default")
      (node (ref "U1") (pin "11") (pinfunction "RC0/T1OSO/T1CKI_11") (pintype "bidirectional"))
      (node (ref "U22") (pin "4") (pinfunction "A_4") (pintype "input"))
      (node (ref "U22") (pin "5") (pinfunction "B_5") (pintype "input"))
    )
    (net (code "80") (name "Net-(U1-RC1{slash}T1OSI{slash}CCP2)") (class "Default")
      (node (ref "U1") (pin "12") (pinfunction "RC1/T1OSI/CCP2_12") (pintype "bidirectional"))
      (node (ref "U22") (pin "1") (pinfunction "A_1") (pintype "input"))
      (node (ref "U22") (pin "2") (pinfunction "B_2") (pintype "input"))
    )
    (net (code "81") (name "Net-(U1-RC2{slash}CCP1)") (class "Default")
      (node (ref "U1") (pin "13") (pinfunction "RC2/CCP1_13") (pintype "bidirectional"))
      (node (ref "U22") (pin "12") (pinfunction "A_12") (pintype "input"))
      (node (ref "U22") (pin "13") (pinfunction "B_13") (pintype "input"))
    )
    (net (code "82") (name "Net-(U1-RC3{slash}SCK{slash}SCL)") (class "Default")
      (node (ref "U1") (pin "14") (pinfunction "RC3/SCK/SCL_14") (pintype "bidirectional"))
      (node (ref "U22") (pin "10") (pinfunction "B_10") (pintype "input"))
      (node (ref "U22") (pin "9") (pinfunction "A_9") (pintype "input"))
    )
    (net (code "83") (name "Net-(U1-RC4{slash}SDI{slash}SDA)") (class "Default")
      (node (ref "U1") (pin "15") (pinfunction "RC4/SDI/SDA_15") (pintype "bidirectional"))
      (node (ref "U23") (pin "1") (pinfunction "A_1") (pintype "input"))
      (node (ref "U23") (pin "2") (pinfunction "B_2") (pintype "input"))
    )
    (net (code "84") (name "Net-(U28031-IN1)") (class "Default")
      (node (ref "PU1") (pin "8") (pinfunction "8_8") (pintype "passive"))
      (node (ref "U28031") (pin "1") (pinfunction "IN1_1") (pintype "input"))
      (node (ref "U5731") (pin "19") (pinfunction "Q1_19") (pintype "tri_state"))
    )
    (net (code "85") (name "Net-(U28031-IN2)") (class "Default")
      (node (ref "PU1") (pin "7") (pinfunction "7_7") (pintype "passive"))
      (node (ref "U28031") (pin "2") (pinfunction "IN2_2") (pintype "input"))
      (node (ref "U5731") (pin "18") (pinfunction "Q2_18") (pintype "tri_state"))
    )
    (net (code "86") (name "Net-(U28031-IN3)") (class "Default")
      (node (ref "PU1") (pin "6") (pinfunction "6_6") (pintype "passive"))
      (node (ref "U28031") (pin "3") (pinfunction "IN3_3") (pintype "input"))
      (node (ref "U5731") (pin "17") (pinfunction "Q3_17") (pintype "tri_state"))
    )
    (net (code "87") (name "Net-(U28031-IN4)") (class "Default")
      (node (ref "PU1") (pin "5") (pinfunction "5_5") (pintype "passive"))
      (node (ref "U28031") (pin "4") (pinfunction "IN4_4") (pintype "input"))
      (node (ref "U5731") (pin "16") (pinfunction "Q4_16") (pintype "tri_state"))
    )
    (net (code "88") (name "Net-(U28031-IN5)") (class "Default")
      (node (ref "PU1") (pin "4") (pinfunction "4_4") (pintype "passive"))
      (node (ref "U28031") (pin "5") (pinfunction "IN5_5") (pintype "input"))
      (node (ref "U5731") (pin "15") (pinfunction "Q5_15") (pintype "tri_state"))
    )
    (net (code "89") (name "Net-(U28031-IN6)") (class "Default")
      (node (ref "PU1") (pin "3") (pinfunction "3_3") (pintype "passive"))
      (node (ref "U28031") (pin "6") (pinfunction "IN6_6") (pintype "input"))
      (node (ref "U5731") (pin "14") (pinfunction "Q6_14") (pintype "tri_state"))
    )
    (net (code "90") (name "Net-(U28031-IN7)") (class "Default")
      (node (ref "PU1") (pin "2") (pinfunction "2_2") (pintype "passive"))
      (node (ref "U28031") (pin "7") (pinfunction "IN7_7") (pintype "input"))
      (node (ref "U5731") (pin "13") (pinfunction "Q7_13") (pintype "tri_state"))
    )
    (net (code "91") (name "Net-(U28031-IN8)") (class "Default")
      (node (ref "PU1") (pin "1") (pinfunction "1_1") (pintype "passive"))
      (node (ref "U28031") (pin "8") (pinfunction "IN8_8") (pintype "input"))
      (node (ref "U5731") (pin "12") (pinfunction "Q8_12") (pintype "tri_state"))
    )
    (net (code "92") (name "Net-(U28032-IN1)") (class "Default")
      (node (ref "PU2") (pin "8") (pinfunction "8_8") (pintype "passive"))
      (node (ref "U28032") (pin "1") (pinfunction "IN1_1") (pintype "input"))
      (node (ref "U5732") (pin "19") (pinfunction "Q1_19") (pintype "tri_state"))
    )
    (net (code "93") (name "Net-(U28032-IN2)") (class "Default")
      (node (ref "PU2") (pin "7") (pinfunction "7_7") (pintype "passive"))
      (node (ref "U28032") (pin "2") (pinfunction "IN2_2") (pintype "input"))
      (node (ref "U5732") (pin "18") (pinfunction "Q2_18") (pintype "tri_state"))
    )
    (net (code "94") (name "Net-(U28032-IN3)") (class "Default")
      (node (ref "PU2") (pin "6") (pinfunction "6_6") (pintype "passive"))
      (node (ref "U28032") (pin "3") (pinfunction "IN3_3") (pintype "input"))
      (node (ref "U5732") (pin "17") (pinfunction "Q3_17") (pintype "tri_state"))
    )
    (net (code "95") (name "Net-(U28032-IN4)") (class "Default")
      (node (ref "PU2") (pin "5") (pinfunction "5_5") (pintype "passive"))
      (node (ref "U28032") (pin "4") (pinfunction "IN4_4") (pintype "input"))
      (node (ref "U5732") (pin "16") (pinfunction "Q4_16") (pintype "tri_state"))
    )
    (net (code "96") (name "Net-(U28032-IN5)") (class "Default")
      (node (ref "PU2") (pin "4") (pinfunction "4_4") (pintype "passive"))
      (node (ref "U28032") (pin "5") (pinfunction "IN5_5") (pintype "input"))
      (node (ref "U5732") (pin "15") (pinfunction "Q5_15") (pintype "tri_state"))
    )
    (net (code "97") (name "Net-(U28032-IN6)") (class "Default")
      (node (ref "PU2") (pin "3") (pinfunction "3_3") (pintype "passive"))
      (node (ref "U28032") (pin "6") (pinfunction "IN6_6") (pintype "input"))
      (node (ref "U5732") (pin "14") (pinfunction "Q6_14") (pintype "tri_state"))
    )
    (net (code "98") (name "Net-(U28032-IN7)") (class "Default")
      (node (ref "PU2") (pin "2") (pinfunction "2_2") (pintype "passive"))
      (node (ref "U28032") (pin "7") (pinfunction "IN7_7") (pintype "input"))
      (node (ref "U5732") (pin "13") (pinfunction "Q7_13") (pintype "tri_state"))
    )
    (net (code "99") (name "Net-(U28032-IN8)") (class "Default")
      (node (ref "PU2") (pin "1") (pinfunction "1_1") (pintype "passive"))
      (node (ref "U28032") (pin "8") (pinfunction "IN8_8") (pintype "input"))
      (node (ref "U5732") (pin "12") (pinfunction "Q8_12") (pintype "tri_state"))
    )
    (net (code "100") (name "Net-(U28033-IN1)") (class "Default")
      (node (ref "PU3") (pin "8") (pinfunction "8_8") (pintype "passive"))
      (node (ref "U28033") (pin "1") (pinfunction "IN1_1") (pintype "input"))
      (node (ref "U5733") (pin "19") (pinfunction "Q1_19") (pintype "tri_state"))
    )
    (net (code "101") (name "Net-(U28033-IN2)") (class "Default")
      (node (ref "PU3") (pin "7") (pinfunction "7_7") (pintype "passive"))
      (node (ref "U28033") (pin "2") (pinfunction "IN2_2") (pintype "input"))
      (node (ref "U5733") (pin "18") (pinfunction "Q2_18") (pintype "tri_state"))
    )
    (net (code "102") (name "Net-(U28033-IN3)") (class "Default")
      (node (ref "PU3") (pin "6") (pinfunction "6_6") (pintype "passive"))
      (node (ref "U28033") (pin "3") (pinfunction "IN3_3") (pintype "input"))
      (node (ref "U5733") (pin "17") (pinfunction "Q3_17") (pintype "tri_state"))
    )
    (net (code "103") (name "Net-(U28033-IN4)") (class "Default")
      (node (ref "PU3") (pin "5") (pinfunction "5_5") (pintype "passive"))
      (node (ref "U28033") (pin "4") (pinfunction "IN4_4") (pintype "input"))
      (node (ref "U5733") (pin "16") (pinfunction "Q4_16") (pintype "tri_state"))
    )
    (net (code "104") (name "Net-(U28033-IN5)") (class "Default")
      (node (ref "PU3") (pin "4") (pinfunction "4_4") (pintype "passive"))
      (node (ref "U28033") (pin "5") (pinfunction "IN5_5") (pintype "input"))
      (node (ref "U5733") (pin "15") (pinfunction "Q5_15") (pintype "tri_state"))
    )
    (net (code "105") (name "Net-(U28033-IN6)") (class "Default")
      (node (ref "PU3") (pin "3") (pinfunction "3_3") (pintype "passive"))
      (node (ref "U28033") (pin "6") (pinfunction "IN6_6") (pintype "input"))
      (node (ref "U5733") (pin "14") (pinfunction "Q6_14") (pintype "tri_state"))
    )
    (net (code "106") (name "Net-(U28033-IN7)") (class "Default")
      (node (ref "PU3") (pin "2") (pinfunction "2_2") (pintype "passive"))
      (node (ref "U28033") (pin "7") (pinfunction "IN7_7") (pintype "input"))
      (node (ref "U5733") (pin "13") (pinfunction "Q7_13") (pintype "tri_state"))
    )
    (net (code "107") (name "Net-(U28033-IN8)") (class "Default")
      (node (ref "PU3") (pin "1") (pinfunction "1_1") (pintype "passive"))
      (node (ref "U28033") (pin "8") (pinfunction "IN8_8") (pintype "input"))
      (node (ref "U5733") (pin "12") (pinfunction "Q8_12") (pintype "tri_state"))
    )
    (net (code "108") (name "Net-(U28034-IN1)") (class "Default")
      (node (ref "PU4") (pin "8") (pinfunction "8_8") (pintype "passive"))
      (node (ref "U28034") (pin "1") (pinfunction "IN1_1") (pintype "input"))
      (node (ref "U5734") (pin "19") (pinfunction "Q1_19") (pintype "tri_state"))
    )
    (net (code "109") (name "Net-(U28034-IN2)") (class "Default")
      (node (ref "PU4") (pin "7") (pinfunction "7_7") (pintype "passive"))
      (node (ref "U28034") (pin "2") (pinfunction "IN2_2") (pintype "input"))
      (node (ref "U5734") (pin "18") (pinfunction "Q2_18") (pintype "tri_state"))
    )
    (net (code "110") (name "Net-(U28034-IN3)") (class "Default")
      (node (ref "PU4") (pin "6") (pinfunction "6_6") (pintype "passive"))
      (node (ref "U28034") (pin "3") (pinfunction "IN3_3") (pintype "input"))
      (node (ref "U5734") (pin "17") (pinfunction "Q3_17") (pintype "tri_state"))
    )
    (net (code "111") (name "Net-(U28034-IN4)") (class "Default")
      (node (ref "PU4") (pin "5") (pinfunction "5_5") (pintype "passive"))
      (node (ref "U28034") (pin "4") (pinfunction "IN4_4") (pintype "input"))
      (node (ref "U5734") (pin "16") (pinfunction "Q4_16") (pintype "tri_state"))
    )
    (net (code "112") (name "Net-(U28034-IN5)") (class "Default")
      (node (ref "PU4") (pin "4") (pinfunction "4_4") (pintype "passive"))
      (node (ref "U28034") (pin "5") (pinfunction "IN5_5") (pintype "input"))
      (node (ref "U5734") (pin "15") (pinfunction "Q5_15") (pintype "tri_state"))
    )
    (net (code "113") (name "Net-(U28034-IN6)") (class "Default")
      (node (ref "PU4") (pin "3") (pinfunction "3_3") (pintype "passive"))
      (node (ref "U28034") (pin "6") (pinfunction "IN6_6") (pintype "input"))
      (node (ref "U5734") (pin "14") (pinfunction "Q6_14") (pintype "tri_state"))
    )
    (net (code "114") (name "Net-(U28034-IN7)") (class "Default")
      (node (ref "PU4") (pin "2") (pinfunction "2_2") (pintype "passive"))
      (node (ref "U28034") (pin "7") (pinfunction "IN7_7") (pintype "input"))
      (node (ref "U5734") (pin "13") (pinfunction "Q7_13") (pintype "tri_state"))
    )
    (net (code "115") (name "Net-(U28034-IN8)") (class "Default")
      (node (ref "PU4") (pin "1") (pinfunction "1_1") (pintype "passive"))
      (node (ref "U28034") (pin "8") (pinfunction "IN8_8") (pintype "input"))
      (node (ref "U5734") (pin "12") (pinfunction "Q8_12") (pintype "tri_state"))
    )
    (net (code "116") (name "Net-(U28035-IN1)") (class "Default")
      (node (ref "PU5") (pin "8") (pinfunction "8_8") (pintype "passive"))
      (node (ref "U28035") (pin "1") (pinfunction "IN1_1") (pintype "input"))
      (node (ref "U5735") (pin "19") (pinfunction "Q1_19") (pintype "tri_state"))
    )
    (net (code "117") (name "Net-(U28035-IN2)") (class "Default")
      (node (ref "PU5") (pin "7") (pinfunction "7_7") (pintype "passive"))
      (node (ref "U28035") (pin "2") (pinfunction "IN2_2") (pintype "input"))
      (node (ref "U5735") (pin "18") (pinfunction "Q2_18") (pintype "tri_state"))
    )
    (net (code "118") (name "Net-(U28035-IN3)") (class "Default")
      (node (ref "PU5") (pin "6") (pinfunction "6_6") (pintype "passive"))
      (node (ref "U28035") (pin "3") (pinfunction "IN3_3") (pintype "input"))
      (node (ref "U5735") (pin "17") (pinfunction "Q3_17") (pintype "tri_state"))
    )
    (net (code "119") (name "Net-(U28035-IN4)") (class "Default")
      (node (ref "PU5") (pin "5") (pinfunction "5_5") (pintype "passive"))
      (node (ref "U28035") (pin "4") (pinfunction "IN4_4") (pintype "input"))
      (node (ref "U5735") (pin "16") (pinfunction "Q4_16") (pintype "tri_state"))
    )
    (net (code "120") (name "Net-(U28035-IN5)") (class "Default")
      (node (ref "PU5") (pin "4") (pinfunction "4_4") (pintype "passive"))
      (node (ref "U28035") (pin "5") (pinfunction "IN5_5") (pintype "input"))
      (node (ref "U5735") (pin "15") (pinfunction "Q5_15") (pintype "tri_state"))
    )
    (net (code "121") (name "Net-(U28035-IN6)") (class "Default")
      (node (ref "PU5") (pin "3") (pinfunction "3_3") (pintype "passive"))
      (node (ref "U28035") (pin "6") (pinfunction "IN6_6") (pintype "input"))
      (node (ref "U5735") (pin "14") (pinfunction "Q6_14") (pintype "tri_state"))
    )
    (net (code "122") (name "Net-(U28035-IN7)") (class "Default")
      (node (ref "PU5") (pin "2") (pinfunction "2_2") (pintype "passive"))
      (node (ref "U28035") (pin "7") (pinfunction "IN7_7") (pintype "input"))
      (node (ref "U5735") (pin "13") (pinfunction "Q7_13") (pintype "tri_state"))
    )
    (net (code "123") (name "Net-(U28035-IN8)") (class "Default")
      (node (ref "PU5") (pin "1") (pinfunction "1_1") (pintype "passive"))
      (node (ref "U28035") (pin "8") (pinfunction "IN8_8") (pintype "input"))
      (node (ref "U5735") (pin "12") (pinfunction "Q8_12") (pintype "tri_state"))
    )
    (net (code "124") (name "VCC") (class "Default")
      (node (ref "C11") (pin "1") (pinfunction "1_1") (pintype "passive"))
      (node (ref "C12") (pin "1") (pinfunction "1_1") (pintype "passive"))
      (node (ref "C13") (pin "1") (pinfunction "1_1") (pintype "passive"))
      (node (ref "C14") (pin "1") (pinfunction "1_1") (pintype "passive"))
      (node (ref "C15") (pin "1") (pinfunction "1_1") (pintype "passive"))
      (node (ref "C17480") (pin "1") (pinfunction "1_1") (pintype "passive"))
      (node (ref "C1P") (pin "1") (pinfunction "1_1") (pintype "passive"))
      (node (ref "C27408") (pin "1") (pinfunction "1_1") (pintype "passive"))
      (node (ref "C37480") (pin "1") (pinfunction "1_1") (pintype "passive"))
      (node (ref "C47408") (pin "1") (pinfunction "1_1") (pintype "passive"))
      (node (ref "C5731") (pin "1") (pinfunction "1_1") (pintype "passive"))
      (node (ref "C5732") (pin "1") (pinfunction "1_1") (pintype "passive"))
      (node (ref "C5733") (pin "1") (pinfunction "1_1") (pintype "passive"))
      (node (ref "C5734") (pin "1") (pinfunction "1_1") (pintype "passive"))
      (node (ref "C5735") (pin "1") (pinfunction "1_1") (pintype "passive"))
      (node (ref "POWER") (pin "1") (pinfunction "1_1") (pintype "passive"))
      (node (ref "PU1") (pin "9") (pinfunction "9_9") (pintype "passive"))
      (node (ref "PU2") (pin "9") (pinfunction "9_9") (pintype "passive"))
      (node (ref "PU3") (pin "9") (pinfunction "9_9") (pintype "passive"))
      (node (ref "PU4") (pin "9") (pinfunction "9_9") (pintype "passive"))
      (node (ref "PU5") (pin "9") (pinfunction "9_9") (pintype "passive"))
      (node (ref "R2") (pin "2") (pinfunction "2_2") (pintype "passive"))
      (node (ref "Rp2") (pin "1") (pinfunction "1_1") (pintype "passive"))
      (node (ref "U2") (pin "14") (pinfunction "VCC_14") (pintype "power_in"))
      (node (ref "U21") (pin "14") (pinfunction "VCC_14") (pintype "power_in"))
      (node (ref "U22") (pin "14") (pinfunction "VCC_14") (pintype "power_in"))
      (node (ref "U23") (pin "14") (pinfunction "VCC_14") (pintype "power_in"))
      (node (ref "U28031") (pin "10") (pinfunction "COM_D_10") (pintype "passive"))
      (node (ref "U28032") (pin "10") (pinfunction "COM_D_10") (pintype "passive"))
      (node (ref "U28033") (pin "10") (pinfunction "COM_D_10") (pintype "passive"))
      (node (ref "U28034") (pin "10") (pinfunction "COM_D_10") (pintype "passive"))
      (node (ref "U28035") (pin "10") (pinfunction "COM_D_10") (pintype "passive"))
      (node (ref "U5731") (pin "20") (pinfunction "VCC_20") (pintype "power_in"))
      (node (ref "U5732") (pin "20") (pinfunction "VCC_20") (pintype "power_in"))
      (node (ref "U5733") (pin "20") (pinfunction "VCC_20") (pintype "power_in"))
      (node (ref "U5734") (pin "20") (pinfunction "VCC_20") (pintype "power_in"))
      (node (ref "U5735") (pin "20") (pinfunction "VCC_20") (pintype "power_in"))
    )
    (net (code "125") (name "unconnected-(U1-RA0{slash}AN0-Pad2)") (class "Default")
      (node (ref "U1") (pin "2") (pinfunction "RA0/AN0_2") (pintype "bidirectional"))
    )
    (net (code "126") (name "unconnected-(U1-RA1{slash}AN1-Pad3)") (class "Default")
      (node (ref "U1") (pin "3") (pinfunction "RA1/AN1_3") (pintype "bidirectional"))
    )
    (net (code "127") (name "unconnected-(U1-RA2{slash}AN2{slash}VREF--Pad4)") (class "Default")
      (node (ref "U1") (pin "4") (pinfunction "RA2/AN2/VREF-_4") (pintype "bidirectional"))
    )
    (net (code "128") (name "unconnected-(U1-RA3{slash}AN3{slash}VREF+-Pad5)") (class "Default")
      (node (ref "U1") (pin "5") (pinfunction "RA3/AN3/VREF+_5") (pintype "bidirectional"))
    )
    (net (code "129") (name "unconnected-(U1-RA4{slash}T0CKI-Pad6)") (class "Default")
      (node (ref "U1") (pin "6") (pinfunction "RA4/T0CKI_6") (pintype "bidirectional"))
    )
    (net (code "130") (name "unconnected-(U1-RA5{slash}AN4{slash}~{SS}{slash}LVDIN-Pad7)") (class "Default")
      (node (ref "U1") (pin "7") (pinfunction "RA5/AN4/~{SS}/LVDIN_7") (pintype "bidirectional"))
    )
    (net (code "131") (name "unconnected-(U1-RC5{slash}SDO-Pad16)") (class "Default")
      (node (ref "U1") (pin "16") (pinfunction "RC5/SDO_16") (pintype "bidirectional+no_connect"))
    )
    (net (code "132") (name "unconnected-(U2A-GND-Pad7)") (class "Default")
      (node (ref "U2") (pin "7") (pinfunction "GND_7") (pintype "power_in"))
    )
    (net (code "133") (name "unconnected-(U2A-VCC-Pad14)") (class "Default")
      (node (ref "U2") (pin "14") (pinfunction "VCC_14") (pintype "power_in"))
    )
    (net (code "134") (name "unconnected-(U2B-GND-Pad7)") (class "Default")
      (node (ref "U2") (pin "7") (pinfunction "GND_7") (pintype "power_in"))
    )
    (net (code "135") (name "unconnected-(U2B-VCC-Pad14)") (class "Default")
      (node (ref "U2") (pin "14") (pinfunction "VCC_14") (pintype "power_in"))
    )
    (net (code "136") (name "unconnected-(U2D-GND-Pad7)") (class "Default")
      (node (ref "U2") (pin "7") (pinfunction "GND_7") (pintype "power_in"))
    )
    (net (code "137") (name "unconnected-(U2D-VCC-Pad14)") (class "Default")
      (node (ref "U2") (pin "14") (pinfunction "VCC_14") (pintype "power_in"))
    )
    (net (code "138") (name "unconnected-(U21A-GND-Pad7)") (class "Default")
      (node (ref "U21") (pin "7") (pinfunction "GND_7") (pintype "power_in"))
    )
    (net (code "139") (name "unconnected-(U21A-VCC-Pad14)") (class "Default")
      (node (ref "U21") (pin "14") (pinfunction "VCC_14") (pintype "power_in"))
    )
    (net (code "140") (name "unconnected-(U21B-GND-Pad7)") (class "Default")
      (node (ref "U21") (pin "7") (pinfunction "GND_7") (pintype "power_in"))
    )
    (net (code "141") (name "unconnected-(U21B-VCC-Pad14)") (class "Default")
      (node (ref "U21") (pin "14") (pinfunction "VCC_14") (pintype "power_in"))
    )
    (net (code "142") (name "unconnected-(U21D-GND-Pad7)") (class "Default")
      (node (ref "U21") (pin "7") (pinfunction "GND_7") (pintype "power_in"))
    )
    (net (code "143") (name "unconnected-(U21D-VCC-Pad14)") (class "Default")
      (node (ref "U21") (pin "14") (pinfunction "VCC_14") (pintype "power_in"))
    )
    (net (code "144") (name "unconnected-(U22A-GND-Pad7)") (class "Default")
      (node (ref "U22") (pin "7") (pinfunction "GND_7") (pintype "power_in"))
    )
    (net (code "145") (name "unconnected-(U22A-VCC-Pad14)") (class "Default")
      (node (ref "U22") (pin "14") (pinfunction "VCC_14") (pintype "power_in"))
    )
    (net (code "146") (name "unconnected-(U22C-GND-Pad7)") (class "Default")
      (node (ref "U22") (pin "7") (pinfunction "GND_7") (pintype "power_in"))
    )
    (net (code "147") (name "unconnected-(U22C-VCC-Pad14)") (class "Default")
      (node (ref "U22") (pin "14") (pinfunction "VCC_14") (pintype "power_in"))
    )
    (net (code "148") (name "unconnected-(U22D-GND-Pad7)") (class "Default")
      (node (ref "U22") (pin "7") (pinfunction "GND_7") (pintype "power_in"))
    )
    (net (code "149") (name "unconnected-(U22D-VCC-Pad14)") (class "Default")
      (node (ref "U22") (pin "14") (pinfunction "VCC_14") (pintype "power_in"))
    )
  )
)
